# Supply_0.net
KiCad netlist of a schematic drawn in Altium Designer
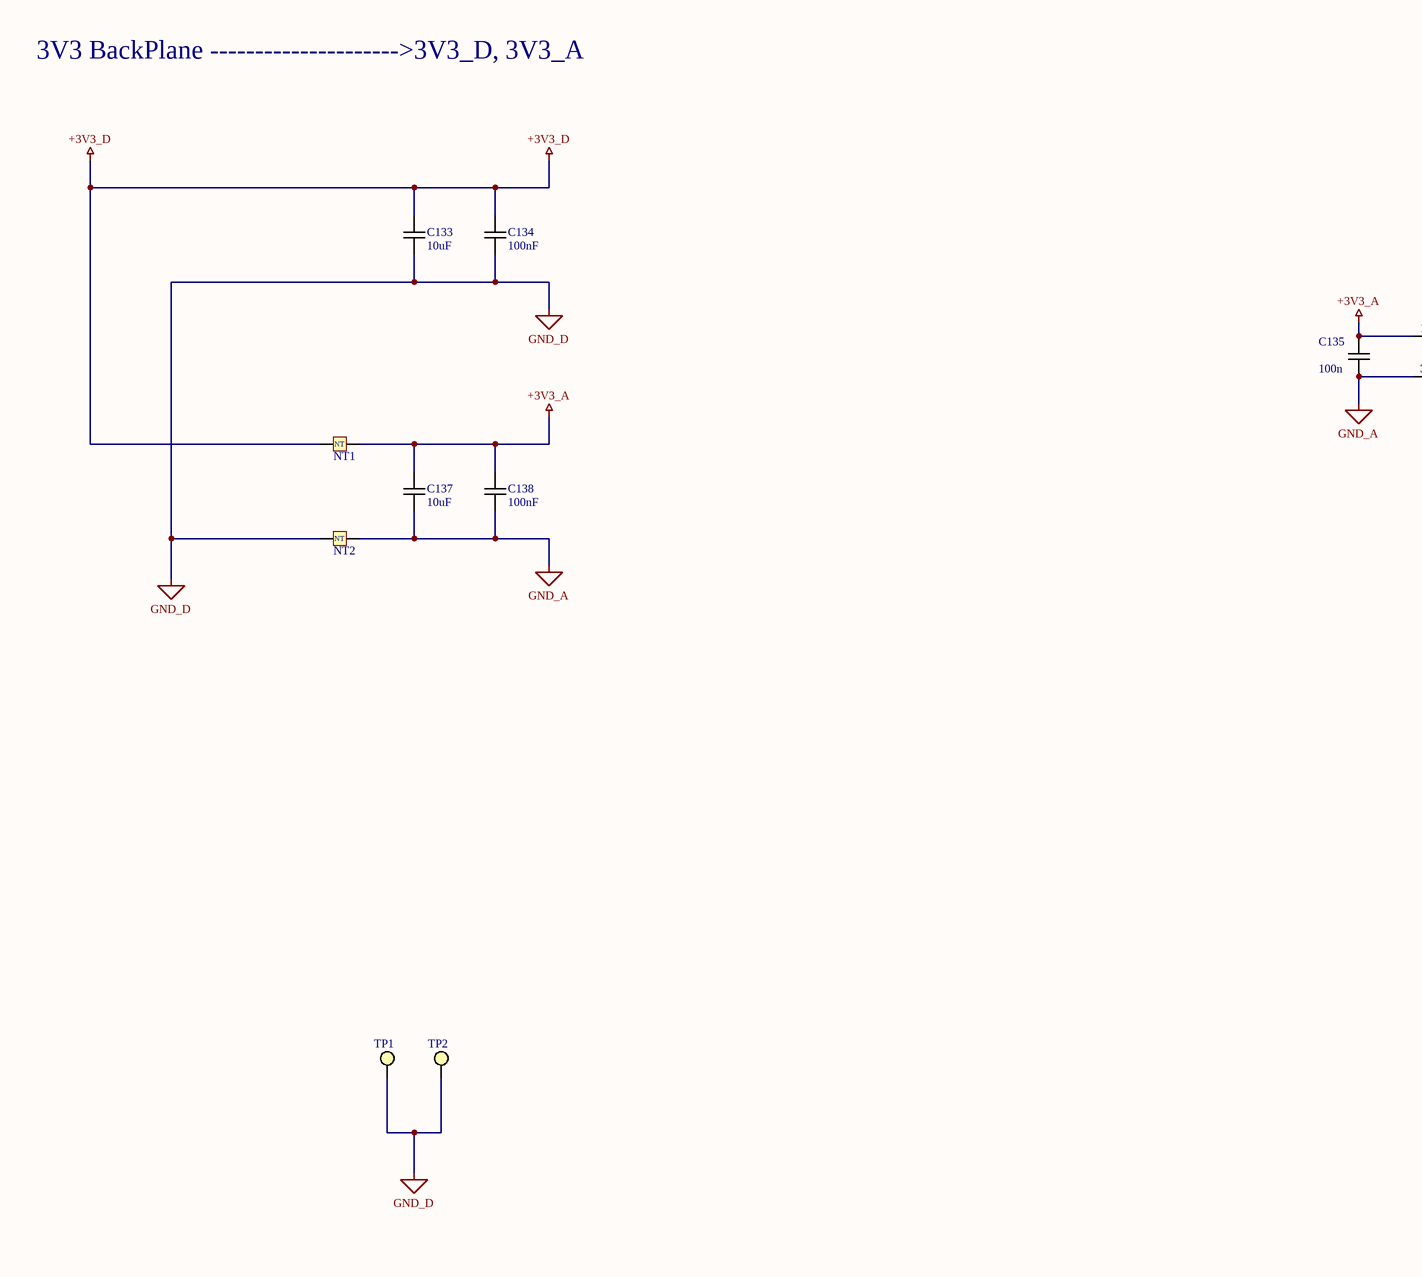
[diagram p0: Supply_0.SchDoc, left]
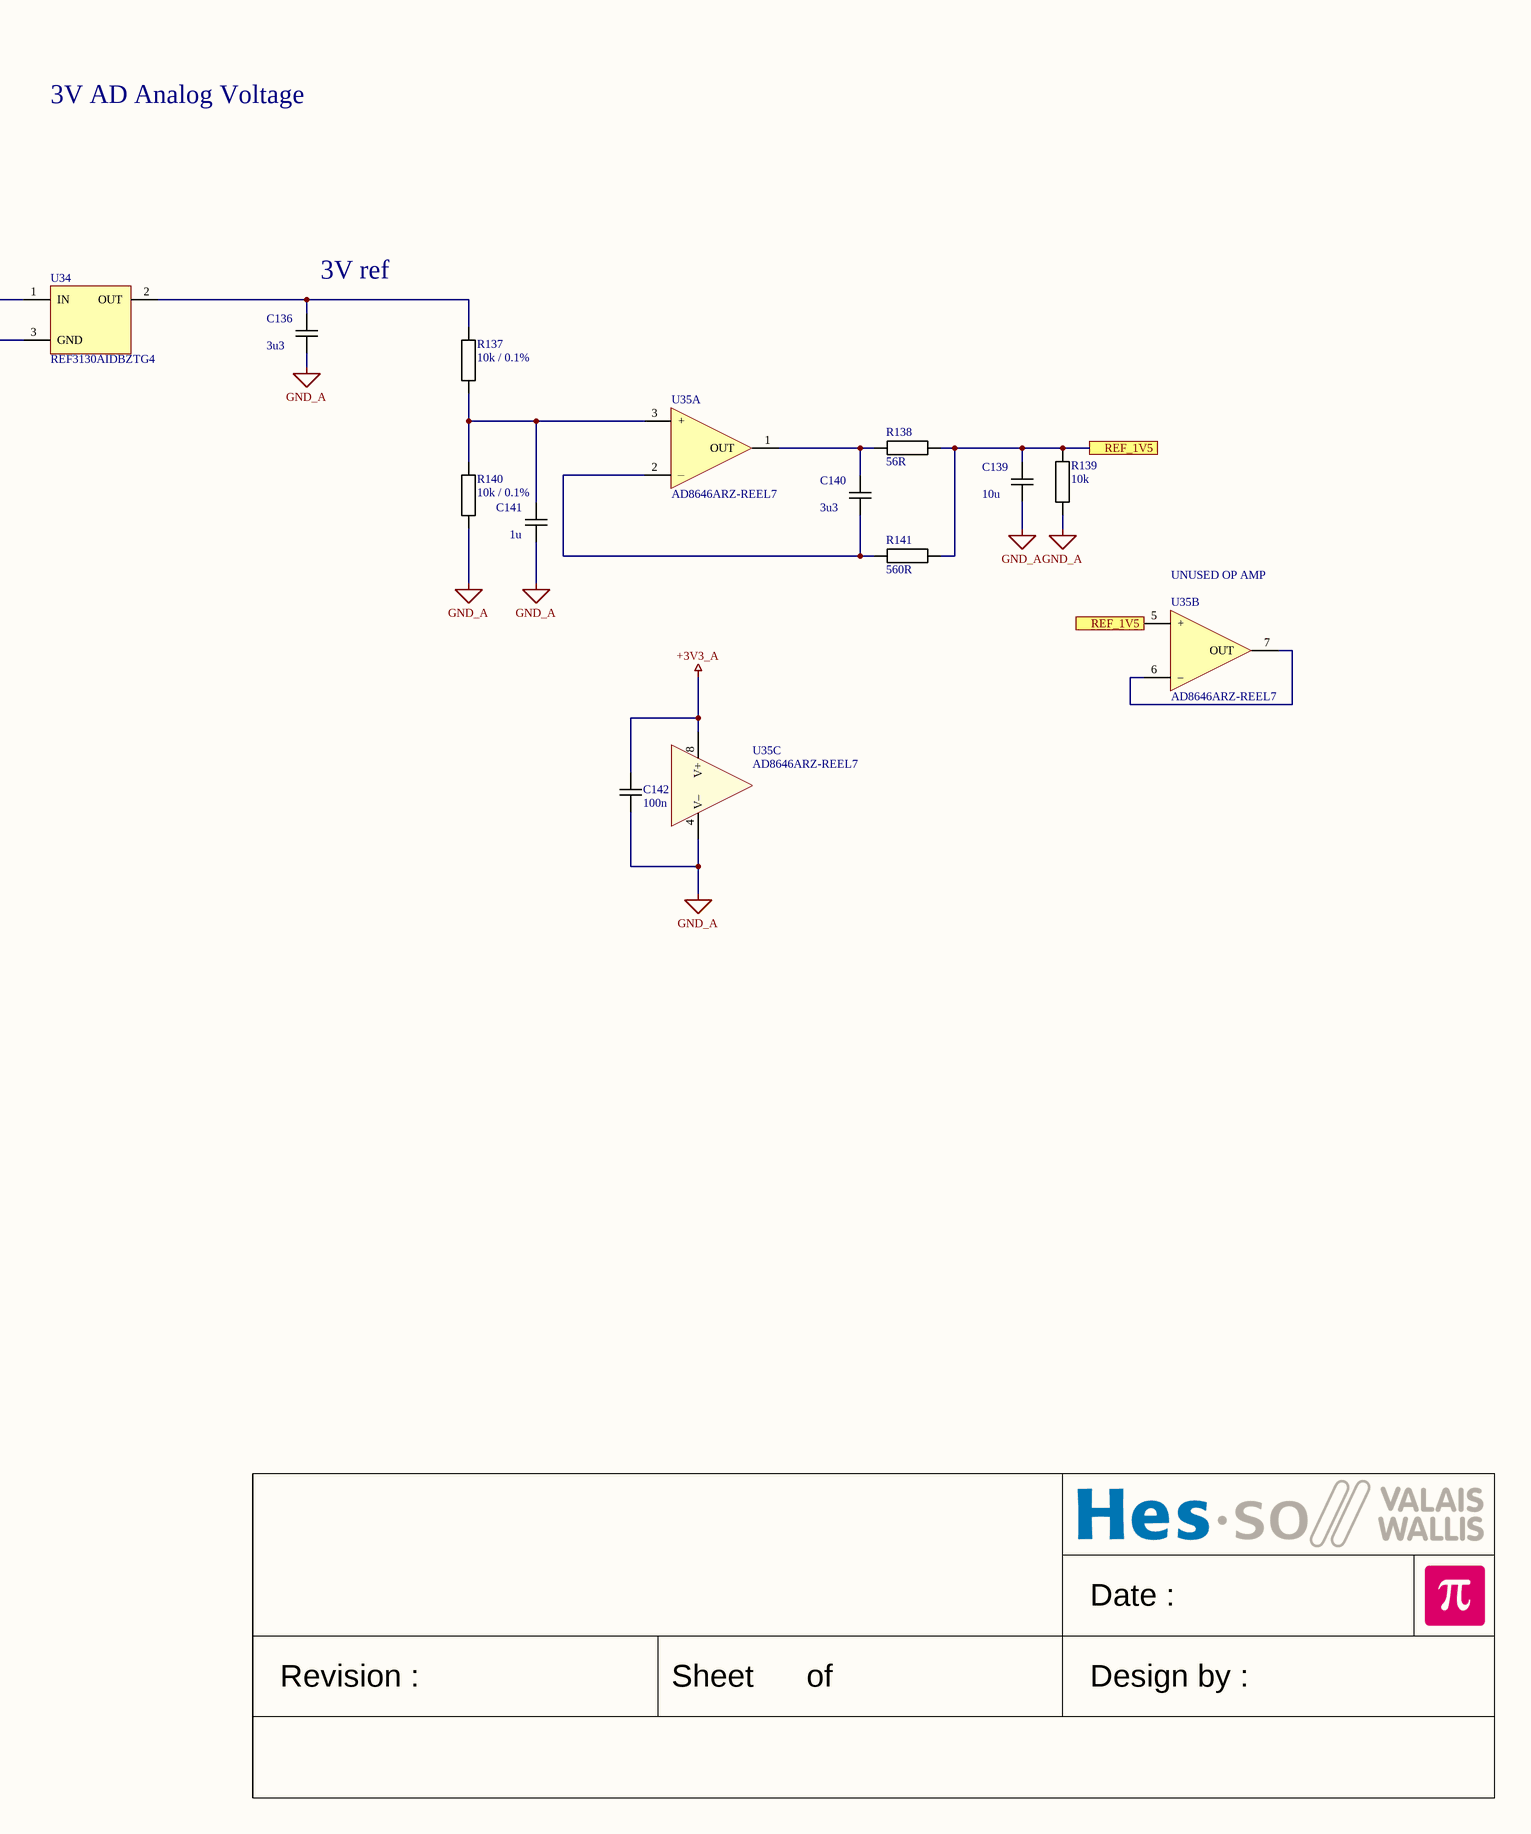
[diagram p1: Supply_0.SchDoc, right]

(export (version "E")
  (design (tool "Eeschema 10.0.6"))
  (components
    (comp (ref "C133")
      (value "10uF")
      (footprint "CAPACITOR 2012 REFLOW")
      (description "Capacitor X7R 10% 10V 2012(0805)")
      (libsource (lib "Capacitor") (part "Capacitor"))
    )
    (comp (ref "C134")
      (value "100nF")
      (footprint "CAPACITOR 2012 REFLOW")
      (description "Capacitor X7R 10% 50V 2012(0805)")
      (libsource (lib "Capacitor") (part "Capacitor"))
    )
    (comp (ref "C135")
      (value "100n")
      (footprint "CAPACITOR 1608 REFLOW")
      (description "Capacitor X7R 10% 50V 1608(0603)")
      (libsource (lib "Capacitor") (part "Capacitor"))
    )
    (comp (ref "C136")
      (value "3u3")
      (footprint "CAPACITOR 2012 REFLOW")
      (description "Capacitor X7R 10% 10V 2012(0805)")
      (libsource (lib "Capacitor") (part "Capacitor"))
    )
    (comp (ref "C137")
      (value "10uF")
      (footprint "CAPACITOR 2012 REFLOW")
      (description "Capacitor X7R 10% 10V 2012(0805)")
      (libsource (lib "Capacitor") (part "Capacitor"))
    )
    (comp (ref "C138")
      (value "100nF")
      (footprint "CAPACITOR 2012 REFLOW")
      (description "Capacitor X7R 10% 50V 2012(0805)")
      (libsource (lib "Capacitor") (part "Capacitor"))
    )
    (comp (ref "C139")
      (value "10u")
      (footprint "CAPACITOR 2012 REFLOW")
      (description "Capacitor X7R 10% 10V 2012(0805)")
      (libsource (lib "Capacitor") (part "Capacitor"))
    )
    (comp (ref "C140")
      (value "3u3")
      (footprint "CAPACITOR 2012 REFLOW")
      (description "Capacitor X7R 10% 10V 2012(0805)")
      (libsource (lib "Capacitor") (part "Capacitor"))
    )
    (comp (ref "C141")
      (value "1u")
      (footprint "CAPACITOR 2012 REFLOW")
      (description "Capacitor X7R 10% 10V 2012(0805)")
      (libsource (lib "Capacitor") (part "Capacitor"))
    )
    (comp (ref "C142")
      (value "100n")
      (footprint "CAPACITOR 1608 REFLOW")
      (description "Capacitor X7R 10% 50V 1608(0603)")
      (libsource (lib "Capacitor") (part "Capacitor"))
    )
    (comp (ref "NT1")
      (value "Net Tie")
      (footprint "NET TIE 1005")
      (description "Connection for 2 different NETNAME")
      (libsource (lib "Jumper") (part "Net Tie"))
    )
    (comp (ref "NT2")
      (value "Net Tie")
      (footprint "NET TIE 1005")
      (description "Connection for 2 different NETNAME")
      (libsource (lib "Jumper") (part "Net Tie"))
    )
    (comp (ref "R137")
      (value "10k / 0.1%")
      (footprint "RESISTOR 1608 REFLOW")
      (description "Resistor 1% 50V 100mW 1608(0603)")
      (libsource (lib "Resistor") (part "Resistor"))
    )
    (comp (ref "R138")
      (value "56R")
      (footprint "RESISTOR 1608 REFLOW")
      (description "Resistor 1% 50V 100mW 1608(0603)")
      (libsource (lib "Resistor") (part "Resistor"))
    )
    (comp (ref "R139")
      (value "10k")
      (footprint "RESISTOR 1608 REFLOW")
      (description "Resistor 1% 50V 100mW 1608(0603)")
      (libsource (lib "Resistor") (part "Resistor"))
    )
    (comp (ref "R140")
      (value "10k / 0.1%")
      (footprint "RESISTOR 1608 REFLOW")
      (description "Resistor 1% 50V 100mW 1608(0603)")
      (libsource (lib "Resistor") (part "Resistor"))
    )
    (comp (ref "R141")
      (value "560R")
      (footprint "RESISTOR 1608 REFLOW")
      (description "Resistor 1% 50V 100mW 1608(0603)")
      (libsource (lib "Resistor") (part "Resistor"))
    )
    (comp (ref "TP1")
      (value "*")
      (footprint "Test Point Keystone Miniature BLACK")
      (description "Test Point")
      (libsource (lib "Testpoint") (part "Test Point"))
    )
    (comp (ref "TP2")
      (value "*")
      (footprint "Test Point Keystone Miniature BLACK")
      (description "Test Point")
      (libsource (lib "Testpoint") (part "Test Point"))
    )
    (comp (ref "U34")
      (value "REF3130AIDBZTG4")
      (footprint "SOT23 P0.95 C1.6x3.0 H1.3")
      (description "Generic Positive Voltage Reference")
      (libsource (lib "Regulator") (part "REFERENCE SOT23 IN,OUT,GND"))
    )
    (comp (ref "U35")
      (value "AD8646ARZ-REEL7")
      (footprint "SO8 P1.27 C4.0X5.0 H1.75")
      (description "Generic dual OPA 8 pins")
      (fields (field (name "MANUFACTURER") "Analog Devices"))
      (libsource (lib "Amplifier") (part "OPA DUAL"))
    )
  )
  (nets
    (net (code "1") (name "+3V3_A") (class "Default")
      (node (ref "C135") (pin "2") (pinfunction "2_2") (pintype "passive"))
      (node (ref "C137") (pin "1") (pinfunction "1_1") (pintype "passive"))
      (node (ref "C138") (pin "1") (pinfunction "1_1") (pintype "passive"))
      (node (ref "C142") (pin "2") (pinfunction "2_2") (pintype "passive"))
      (node (ref "NT1") (pin "2") (pinfunction "2_2") (pintype "passive"))
      (node (ref "U34") (pin "1") (pinfunction "IN_1") (pintype "passive"))
      (node (ref "U35") (pin "8") (pinfunction "V+_8") (pintype "passive"))
    )
    (net (code "2") (name "+3V3_D") (class "Default")
      (node (ref "C133") (pin "1") (pinfunction "1_1") (pintype "passive"))
      (node (ref "C134") (pin "1") (pinfunction "1_1") (pintype "passive"))
      (node (ref "NT1") (pin "1") (pinfunction "1_1") (pintype "passive"))
    )
    (net (code "3") (name "/REF_1V5") (class "Default")
      (node (ref "C139") (pin "2") (pinfunction "2_2") (pintype "passive"))
      (node (ref "R138") (pin "1") (pinfunction "1_1") (pintype "passive"))
      (node (ref "R139") (pin "1") (pinfunction "1_1") (pintype "passive"))
      (node (ref "R141") (pin "1") (pinfunction "1_1") (pintype "passive"))
      (node (ref "U35") (pin "5") (pinfunction "+_5") (pintype "passive"))
    )
    (net (code "4") (name "GND_A") (class "Default")
      (node (ref "C135") (pin "1") (pinfunction "1_1") (pintype "passive"))
      (node (ref "C136") (pin "1") (pinfunction "1_1") (pintype "passive"))
      (node (ref "C137") (pin "2") (pinfunction "2_2") (pintype "passive"))
      (node (ref "C138") (pin "2") (pinfunction "2_2") (pintype "passive"))
      (node (ref "C139") (pin "1") (pinfunction "1_1") (pintype "passive"))
      (node (ref "C141") (pin "1") (pinfunction "1_1") (pintype "passive"))
      (node (ref "C142") (pin "1") (pinfunction "1_1") (pintype "passive"))
      (node (ref "NT2") (pin "2") (pinfunction "2_2") (pintype "passive"))
      (node (ref "R139") (pin "2") (pinfunction "2_2") (pintype "passive"))
      (node (ref "R140") (pin "2") (pinfunction "2_2") (pintype "passive"))
      (node (ref "U34") (pin "3") (pinfunction "GND_3") (pintype "passive"))
      (node (ref "U35") (pin "4") (pinfunction "V–_4") (pintype "passive"))
    )
    (net (code "5") (name "GND_D") (class "Default")
      (node (ref "C133") (pin "2") (pinfunction "2_2") (pintype "passive"))
      (node (ref "C134") (pin "2") (pinfunction "2_2") (pintype "passive"))
      (node (ref "NT2") (pin "1") (pinfunction "1_1") (pintype "passive"))
      (node (ref "TP1") (pin "1") (pinfunction "1_1") (pintype "passive"))
      (node (ref "TP2") (pin "1") (pinfunction "1_1") (pintype "passive"))
    )
    (net (code "6") (name "Net-(U34-OUT)") (class "Default")
      (node (ref "C136") (pin "2") (pinfunction "2_2") (pintype "passive"))
      (node (ref "R137") (pin "2") (pinfunction "2_2") (pintype "passive"))
      (node (ref "U34") (pin "2") (pinfunction "OUT_2") (pintype "passive"))
    )
    (net (code "7") (name "Net-(U35A-+)") (class "Default")
      (node (ref "C141") (pin "2") (pinfunction "2_2") (pintype "passive"))
      (node (ref "R137") (pin "1") (pinfunction "1_1") (pintype "passive"))
      (node (ref "R140") (pin "1") (pinfunction "1_1") (pintype "passive"))
      (node (ref "U35") (pin "3") (pinfunction "+_3") (pintype "passive"))
    )
    (net (code "8") (name "Net-(U35A-OUT)") (class "Default")
      (node (ref "C140") (pin "2") (pinfunction "2_2") (pintype "passive"))
      (node (ref "R138") (pin "2") (pinfunction "2_2") (pintype "passive"))
      (node (ref "U35") (pin "1") (pinfunction "OUT_1") (pintype "passive"))
    )
    (net (code "9") (name "Net-(U35A-–)") (class "Default")
      (node (ref "C140") (pin "1") (pinfunction "1_1") (pintype "passive"))
      (node (ref "R141") (pin "2") (pinfunction "2_2") (pintype "passive"))
      (node (ref "U35") (pin "2") (pinfunction "–_2") (pintype "passive"))
    )
    (net (code "10") (name "Net-(U35B-OUT)") (class "Default")
      (node (ref "U35") (pin "6") (pinfunction "–_6") (pintype "passive"))
      (node (ref "U35") (pin "7") (pinfunction "OUT_7") (pintype "passive"))
    )
  )
)
